# HAL_4.net
KiCad netlist of a schematic drawn in Altium Designer
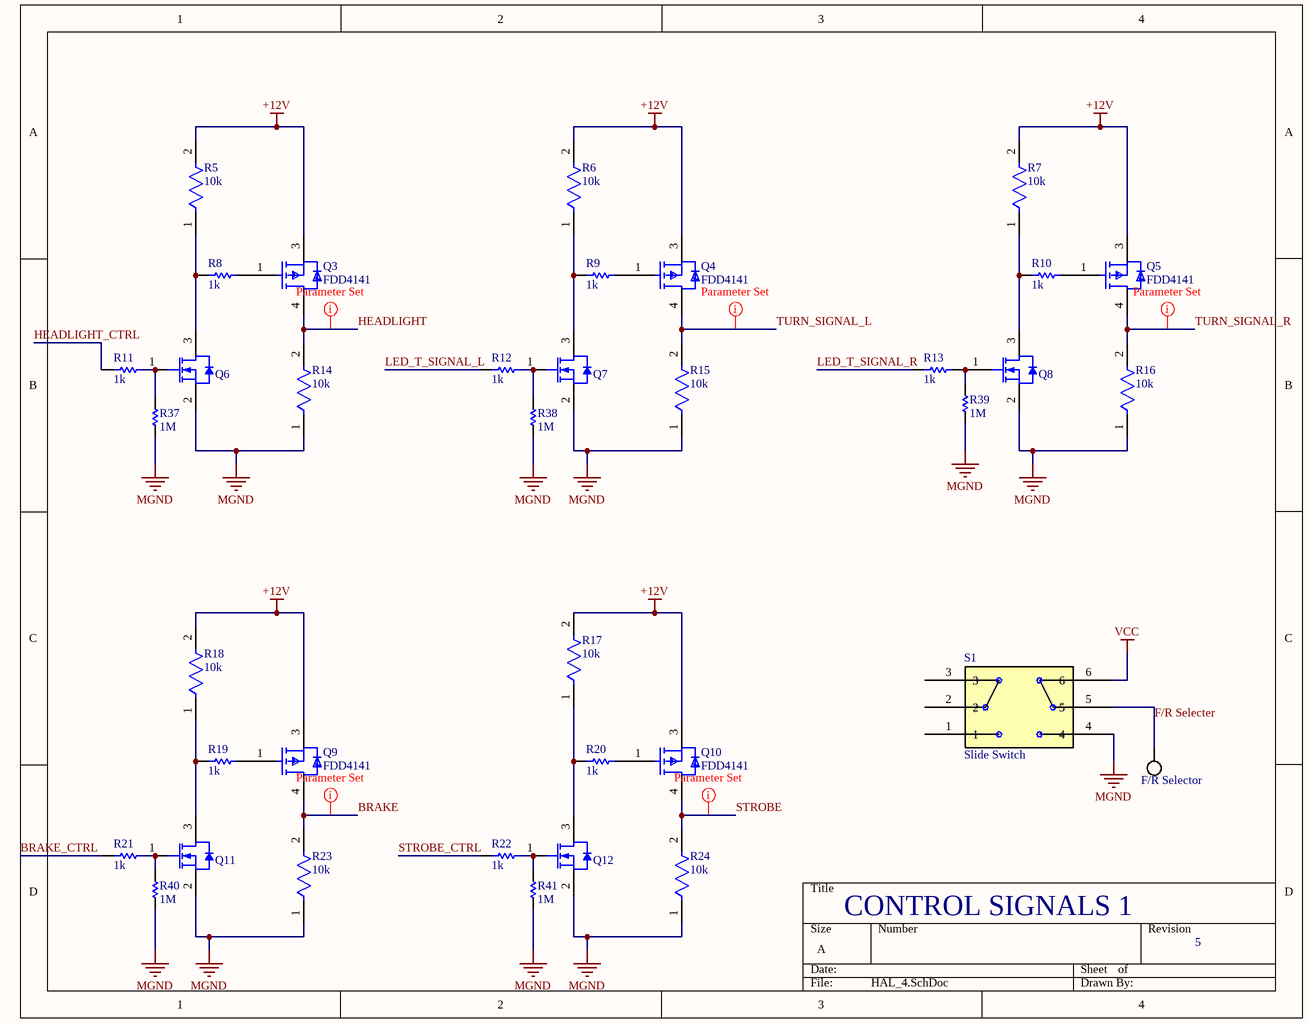
[diagram p0: HAL_4.SchDoc]

(export (version "E")
  (design (tool "Eeschema 10.0.6"))
  (components
    (comp (ref "F/R Selector")
      (value "F/R Selector")
      (footprint "EPAD")
      (description "Pad for probing signals")
      (libsource (lib "PrISUm-Discrete") (part "EPAD"))
    )
    (comp (ref "Q3")
      (value "FDD4141")
      (footprint "FP-369AS-MFG")
      (description "MOSFET P-CH 40V 10.8A DPAK")
      (fields
        (field (name "OCTOPART") "https://octopart.com/fdd4141-on+semiconductor-84325802")
        (field (name "MANUFACTURER") "ON Semiconductor")
      )
      (libsource (lib "Altium Content Vault") (part "ec195c925100855187fe8c06440c3e1"))
    )
    (comp (ref "Q4")
      (value "FDD4141")
      (footprint "FP-369AS-MFG")
      (description "MOSFET P-CH 40V 10.8A DPAK")
      (fields
        (field (name "OCTOPART") "https://octopart.com/fdd4141-on+semiconductor-84325802")
        (field (name "MANUFACTURER") "ON Semiconductor")
      )
      (libsource (lib "Altium Content Vault") (part "ec195c925100855187fe8c06440c3e1"))
    )
    (comp (ref "Q5")
      (value "FDD4141")
      (footprint "FP-369AS-MFG")
      (description "MOSFET P-CH 40V 10.8A DPAK")
      (fields
        (field (name "OCTOPART") "https://octopart.com/fdd4141-on+semiconductor-84325802")
        (field (name "MANUFACTURER") "ON Semiconductor")
      )
      (libsource (lib "Altium Content Vault") (part "ec195c925100855187fe8c06440c3e1"))
    )
    (comp (ref "Q6")
      (value "NTR4501NT1G")
      (footprint "ONSC-SOT-23-3-318-08_V")
      (description "Power MOSFET, 20 V, 3.2 A, Single N-Channel, 3-Pin SOT-23, Pb-Free, Tape and Reel")
      (fields (field (name "MANUFACTURER") "On Semiconductor"))
      (libsource (lib "Altium Content Vault") (part "ONSC-NMOS-G1S2D3-3"))
    )
    (comp (ref "Q7")
      (value "NTR4501NT1G")
      (footprint "ONSC-SOT-23-3-318-08_V")
      (description "Power MOSFET, 20 V, 3.2 A, Single N-Channel, 3-Pin SOT-23, Pb-Free, Tape and Reel")
      (fields (field (name "MANUFACTURER") "On Semiconductor"))
      (libsource (lib "Altium Content Vault") (part "ONSC-NMOS-G1S2D3-3"))
    )
    (comp (ref "Q8")
      (value "NTR4501NT1G")
      (footprint "ONSC-SOT-23-3-318-08_V")
      (description "Power MOSFET, 20 V, 3.2 A, Single N-Channel, 3-Pin SOT-23, Pb-Free, Tape and Reel")
      (fields (field (name "MANUFACTURER") "On Semiconductor"))
      (libsource (lib "Altium Content Vault") (part "ONSC-NMOS-G1S2D3-3"))
    )
    (comp (ref "Q9")
      (value "FDD4141")
      (footprint "FP-369AS-MFG")
      (description "MOSFET P-CH 40V 10.8A DPAK")
      (fields
        (field (name "OCTOPART") "https://octopart.com/fdd4141-on+semiconductor-84325802")
        (field (name "MANUFACTURER") "ON Semiconductor")
      )
      (libsource (lib "Altium Content Vault") (part "ec195c925100855187fe8c06440c3e1"))
    )
    (comp (ref "Q10")
      (value "FDD4141")
      (footprint "FP-369AS-MFG")
      (description "MOSFET P-CH 40V 10.8A DPAK")
      (fields
        (field (name "OCTOPART") "https://octopart.com/fdd4141-on+semiconductor-84325802")
        (field (name "MANUFACTURER") "ON Semiconductor")
      )
      (libsource (lib "Altium Content Vault") (part "ec195c925100855187fe8c06440c3e1"))
    )
    (comp (ref "Q11")
      (value "NTR4501NT1G")
      (footprint "ONSC-SOT-23-3-318-08_V")
      (description "Power MOSFET, 20 V, 3.2 A, Single N-Channel, 3-Pin SOT-23, Pb-Free, Tape and Reel")
      (fields (field (name "MANUFACTURER") "On Semiconductor"))
      (libsource (lib "Altium Content Vault") (part "ONSC-NMOS-G1S2D3-3"))
    )
    (comp (ref "Q12")
      (value "NTR4501NT1G")
      (footprint "ONSC-SOT-23-3-318-08_V")
      (description "Power MOSFET, 20 V, 3.2 A, Single N-Channel, 3-Pin SOT-23, Pb-Free, Tape and Reel")
      (fields (field (name "MANUFACTURER") "On Semiconductor"))
      (libsource (lib "Altium Content Vault") (part "ONSC-NMOS-G1S2D3-3"))
    )
    (comp (ref "R5")
      (value "10k")
      (footprint "FP-RMCF0805-MFG")
      (description "RES 10K OHM 1% 1/8W 0805")
      (fields (field (name "TOLERANCE") "1%"))
      (libsource (lib "Altium Content Vault") (part "1029c3af85768c4190bb7ad29bc67b5"))
    )
    (comp (ref "R6")
      (value "10k")
      (footprint "FP-RMCF0805-MFG")
      (description "RES 10K OHM 1% 1/8W 0805")
      (fields (field (name "TOLERANCE") "1%"))
      (libsource (lib "Altium Content Vault") (part "1029c3af85768c4190bb7ad29bc67b5"))
    )
    (comp (ref "R7")
      (value "10k")
      (footprint "FP-RMCF0805-MFG")
      (description "RES 10K OHM 1% 1/8W 0805")
      (fields (field (name "TOLERANCE") "1%"))
      (libsource (lib "Altium Content Vault") (part "1029c3af85768c4190bb7ad29bc67b5"))
    )
    (comp (ref "R8")
      (value "1k")
      (footprint "RESC3216X70X40LL20T20")
      (description "RK73B2BTTD102J")
      (fields (field (name "MANUFACTURER") "KOA Speer"))
      (libsource (lib "Altium Content Vault") (part "RES"))
    )
    (comp (ref "R9")
      (value "1k")
      (footprint "RESC3216X70X40LL20T20")
      (description "RK73B2BTTD102J")
      (fields (field (name "MANUFACTURER") "KOA Speer"))
      (libsource (lib "Altium Content Vault") (part "RES"))
    )
    (comp (ref "R10")
      (value "1k")
      (footprint "RESC3216X70X40LL20T20")
      (description "RK73B2BTTD102J")
      (fields (field (name "MANUFACTURER") "KOA Speer"))
      (libsource (lib "Altium Content Vault") (part "RES"))
    )
    (comp (ref "R11")
      (value "1k")
      (footprint "RESC3216X70X40LL20T20")
      (description "RK73B2BTTD102J")
      (fields (field (name "MANUFACTURER") "KOA Speer"))
      (libsource (lib "Altium Content Vault") (part "RES"))
    )
    (comp (ref "R12")
      (value "1k")
      (footprint "RESC3216X70X40LL20T20")
      (description "RK73B2BTTD102J")
      (fields (field (name "MANUFACTURER") "KOA Speer"))
      (libsource (lib "Altium Content Vault") (part "RES"))
    )
    (comp (ref "R13")
      (value "1k")
      (footprint "RESC3216X70X40LL20T20")
      (description "RK73B2BTTD102J")
      (fields (field (name "MANUFACTURER") "KOA Speer"))
      (libsource (lib "Altium Content Vault") (part "RES"))
    )
    (comp (ref "R14")
      (value "10k")
      (footprint "FP-RMCF0805-MFG")
      (description "RES 10K OHM 1% 1/8W 0805")
      (fields (field (name "TOLERANCE") "1%"))
      (libsource (lib "Altium Content Vault") (part "1029c3af85768c4190bb7ad29bc67b5"))
    )
    (comp (ref "R15")
      (value "10k")
      (footprint "FP-RMCF0805-MFG")
      (description "RES 10K OHM 1% 1/8W 0805")
      (fields (field (name "TOLERANCE") "1%"))
      (libsource (lib "Altium Content Vault") (part "1029c3af85768c4190bb7ad29bc67b5"))
    )
    (comp (ref "R16")
      (value "10k")
      (footprint "FP-RMCF0805-MFG")
      (description "RES 10K OHM 1% 1/8W 0805")
      (fields (field (name "TOLERANCE") "1%"))
      (libsource (lib "Altium Content Vault") (part "1029c3af85768c4190bb7ad29bc67b5"))
    )
    (comp (ref "R17")
      (value "10k")
      (footprint "FP-RMCF0805-MFG")
      (description "RES 10K OHM 1% 1/8W 0805")
      (fields (field (name "TOLERANCE") "1%"))
      (libsource (lib "Altium Content Vault") (part "1029c3af85768c4190bb7ad29bc67b5"))
    )
    (comp (ref "R18")
      (value "10k")
      (footprint "FP-RMCF0805-MFG")
      (description "RES 10K OHM 1% 1/8W 0805")
      (fields (field (name "TOLERANCE") "1%"))
      (libsource (lib "Altium Content Vault") (part "1029c3af85768c4190bb7ad29bc67b5"))
    )
    (comp (ref "R19")
      (value "1k")
      (footprint "RESC3216X70X40LL20T20")
      (description "RK73B2BTTD102J")
      (fields (field (name "MANUFACTURER") "KOA Speer"))
      (libsource (lib "Altium Content Vault") (part "RES"))
    )
    (comp (ref "R20")
      (value "1k")
      (footprint "RESC3216X70X40LL20T20")
      (description "RK73B2BTTD102J")
      (fields (field (name "MANUFACTURER") "KOA Speer"))
      (libsource (lib "Altium Content Vault") (part "RES"))
    )
    (comp (ref "R21")
      (value "1k")
      (footprint "RESC3216X70X40LL20T20")
      (description "RK73B2BTTD102J")
      (fields (field (name "MANUFACTURER") "KOA Speer"))
      (libsource (lib "Altium Content Vault") (part "RES"))
    )
    (comp (ref "R22")
      (value "1k")
      (footprint "RESC3216X70X40LL20T20")
      (description "RK73B2BTTD102J")
      (fields (field (name "MANUFACTURER") "KOA Speer"))
      (libsource (lib "Altium Content Vault") (part "RES"))
    )
    (comp (ref "R23")
      (value "10k")
      (footprint "FP-RMCF0805-MFG")
      (description "RES 10K OHM 1% 1/8W 0805")
      (fields (field (name "TOLERANCE") "1%"))
      (libsource (lib "Altium Content Vault") (part "1029c3af85768c4190bb7ad29bc67b5"))
    )
    (comp (ref "R24")
      (value "10k")
      (footprint "FP-RMCF0805-MFG")
      (description "RES 10K OHM 1% 1/8W 0805")
      (fields (field (name "TOLERANCE") "1%"))
      (libsource (lib "Altium Content Vault") (part "1029c3af85768c4190bb7ad29bc67b5"))
    )
    (comp (ref "R37")
      (value "1M")
      (footprint "0603_B")
      (description "0603 1MOhm resistor")
      (fields (field (name "Comment") "CRCW06031M00FKEA"))
      (libsource (lib "Resistors") (part "CRCW06031M00FKEA"))
    )
    (comp (ref "R38")
      (value "1M")
      (footprint "0603_B")
      (description "0603 1MOhm resistor")
      (fields (field (name "Comment") "CRCW06031M00FKEA"))
      (libsource (lib "Resistors") (part "CRCW06031M00FKEA"))
    )
    (comp (ref "R39")
      (value "1M")
      (footprint "0603_B")
      (description "0603 1MOhm resistor")
      (fields (field (name "Comment") "CRCW06031M00FKEA"))
      (libsource (lib "Resistors") (part "CRCW06031M00FKEA"))
    )
    (comp (ref "R40")
      (value "1M")
      (footprint "0603_B")
      (description "0603 1MOhm resistor")
      (fields (field (name "Comment") "CRCW06031M00FKEA"))
      (libsource (lib "Resistors") (part "CRCW06031M00FKEA"))
    )
    (comp (ref "R41")
      (value "1M")
      (footprint "0603_B")
      (description "0603 1MOhm resistor")
      (fields (field (name "Comment") "CRCW06031M00FKEA"))
      (libsource (lib "Resistors") (part "CRCW06031M00FKEA"))
    )
    (comp (ref "S1")
      (value "Slide Switch")
      (footprint "DPDT Switch")
      (libsource (lib "PrISUm-Discrete") (part "Slide Switch"))
    )
  )
  (nets
    (net (code "1") (name "+12V") (class "Default")
      (node (ref "Q10") (pin "3") (pinfunction "S_3") (pintype "passive"))
      (node (ref "Q3") (pin "3") (pinfunction "S_3") (pintype "passive"))
      (node (ref "Q4") (pin "3") (pinfunction "S_3") (pintype "passive"))
      (node (ref "Q5") (pin "3") (pinfunction "S_3") (pintype "passive"))
      (node (ref "Q9") (pin "3") (pinfunction "S_3") (pintype "passive"))
      (node (ref "R17") (pin "2") (pinfunction "2_2") (pintype "passive"))
      (node (ref "R18") (pin "2") (pinfunction "2_2") (pintype "passive"))
      (node (ref "R5") (pin "2") (pinfunction "2_2") (pintype "passive"))
      (node (ref "R6") (pin "2") (pinfunction "2_2") (pintype "passive"))
      (node (ref "R7") (pin "2") (pinfunction "2_2") (pintype "passive"))
    )
    (net (code "2") (name "/BRAKE") (class "Default")
      (node (ref "Q9") (pin "4") (pinfunction "D_4") (pintype "passive"))
      (node (ref "R23") (pin "2") (pinfunction "2_2") (pintype "passive"))
    )
    (net (code "3") (name "/BRAKE_CTRL") (class "Default")
      (node (ref "R21") (pin "1") (pinfunction "1_1") (pintype "passive"))
    )
    (net (code "4") (name "/F{slash}R Selecter") (class "Default")
      (node (ref "F/R Selector") (pin "1") (pinfunction "1_1") (pintype "passive"))
      (node (ref "S1") (pin "5") (pinfunction "5_5") (pintype "passive"))
    )
    (net (code "5") (name "/HEADLIGHT") (class "Default")
      (node (ref "Q3") (pin "4") (pinfunction "D_4") (pintype "passive"))
      (node (ref "R14") (pin "2") (pinfunction "2_2") (pintype "passive"))
    )
    (net (code "6") (name "/HEADLIGHT_CTRL") (class "Default")
      (node (ref "R11") (pin "1") (pinfunction "1_1") (pintype "passive"))
    )
    (net (code "7") (name "/LED_T_SIGNAL_L") (class "Default")
      (node (ref "R12") (pin "1") (pinfunction "1_1") (pintype "passive"))
    )
    (net (code "8") (name "/LED_T_SIGNAL_R") (class "Default")
      (node (ref "R13") (pin "1") (pinfunction "1_1") (pintype "passive"))
    )
    (net (code "9") (name "/STROBE") (class "Default")
      (node (ref "Q10") (pin "4") (pinfunction "D_4") (pintype "passive"))
      (node (ref "R24") (pin "2") (pinfunction "2_2") (pintype "passive"))
    )
    (net (code "10") (name "/STROBE_CTRL") (class "Default")
      (node (ref "R22") (pin "1") (pinfunction "1_1") (pintype "passive"))
    )
    (net (code "11") (name "/TURN_SIGNAL_L") (class "Default")
      (node (ref "Q4") (pin "4") (pinfunction "D_4") (pintype "passive"))
      (node (ref "R15") (pin "2") (pinfunction "2_2") (pintype "passive"))
    )
    (net (code "12") (name "/TURN_SIGNAL_R") (class "Default")
      (node (ref "Q5") (pin "4") (pinfunction "D_4") (pintype "passive"))
      (node (ref "R16") (pin "2") (pinfunction "2_2") (pintype "passive"))
    )
    (net (code "13") (name "MGND") (class "Default")
      (node (ref "Q11") (pin "2") (pinfunction "S_2") (pintype "passive"))
      (node (ref "Q12") (pin "2") (pinfunction "S_2") (pintype "passive"))
      (node (ref "Q6") (pin "2") (pinfunction "S_2") (pintype "passive"))
      (node (ref "Q7") (pin "2") (pinfunction "S_2") (pintype "passive"))
      (node (ref "Q8") (pin "2") (pinfunction "S_2") (pintype "passive"))
      (node (ref "R14") (pin "1") (pinfunction "1_1") (pintype "passive"))
      (node (ref "R15") (pin "1") (pinfunction "1_1") (pintype "passive"))
      (node (ref "R16") (pin "1") (pinfunction "1_1") (pintype "passive"))
      (node (ref "R23") (pin "1") (pinfunction "1_1") (pintype "passive"))
      (node (ref "R24") (pin "1") (pinfunction "1_1") (pintype "passive"))
      (node (ref "R37") (pin "1") (pinfunction "1_1") (pintype "passive"))
      (node (ref "R38") (pin "1") (pinfunction "1_1") (pintype "passive"))
      (node (ref "R39") (pin "1") (pinfunction "1_1") (pintype "passive"))
      (node (ref "R40") (pin "1") (pinfunction "1_1") (pintype "passive"))
      (node (ref "R41") (pin "1") (pinfunction "1_1") (pintype "passive"))
      (node (ref "S1") (pin "4") (pinfunction "4_4") (pintype "passive"))
    )
    (net (code "14") (name "Net-(Q3-G)") (class "Default")
      (node (ref "Q3") (pin "1") (pinfunction "G_1") (pintype "passive"))
      (node (ref "R8") (pin "2") (pinfunction "2_2") (pintype "passive"))
    )
    (net (code "15") (name "Net-(Q4-G)") (class "Default")
      (node (ref "Q4") (pin "1") (pinfunction "G_1") (pintype "passive"))
      (node (ref "R9") (pin "2") (pinfunction "2_2") (pintype "passive"))
    )
    (net (code "16") (name "Net-(Q5-G)") (class "Default")
      (node (ref "Q5") (pin "1") (pinfunction "G_1") (pintype "passive"))
      (node (ref "R10") (pin "2") (pinfunction "2_2") (pintype "passive"))
    )
    (net (code "17") (name "Net-(Q6-D)") (class "Default")
      (node (ref "Q6") (pin "3") (pinfunction "D_3") (pintype "passive"))
      (node (ref "R5") (pin "1") (pinfunction "1_1") (pintype "passive"))
      (node (ref "R8") (pin "1") (pinfunction "1_1") (pintype "passive"))
    )
    (net (code "18") (name "Net-(Q6-G)") (class "Default")
      (node (ref "Q6") (pin "1") (pinfunction "G_1") (pintype "passive"))
      (node (ref "R11") (pin "2") (pinfunction "2_2") (pintype "passive"))
      (node (ref "R37") (pin "2") (pinfunction "2_2") (pintype "passive"))
    )
    (net (code "19") (name "Net-(Q7-D)") (class "Default")
      (node (ref "Q7") (pin "3") (pinfunction "D_3") (pintype "passive"))
      (node (ref "R6") (pin "1") (pinfunction "1_1") (pintype "passive"))
      (node (ref "R9") (pin "1") (pinfunction "1_1") (pintype "passive"))
    )
    (net (code "20") (name "Net-(Q7-G)") (class "Default")
      (node (ref "Q7") (pin "1") (pinfunction "G_1") (pintype "passive"))
      (node (ref "R12") (pin "2") (pinfunction "2_2") (pintype "passive"))
      (node (ref "R38") (pin "2") (pinfunction "2_2") (pintype "passive"))
    )
    (net (code "21") (name "Net-(Q8-D)") (class "Default")
      (node (ref "Q8") (pin "3") (pinfunction "D_3") (pintype "passive"))
      (node (ref "R10") (pin "1") (pinfunction "1_1") (pintype "passive"))
      (node (ref "R7") (pin "1") (pinfunction "1_1") (pintype "passive"))
    )
    (net (code "22") (name "Net-(Q8-G)") (class "Default")
      (node (ref "Q8") (pin "1") (pinfunction "G_1") (pintype "passive"))
      (node (ref "R13") (pin "2") (pinfunction "2_2") (pintype "passive"))
      (node (ref "R39") (pin "2") (pinfunction "2_2") (pintype "passive"))
    )
    (net (code "23") (name "Net-(Q9-G)") (class "Default")
      (node (ref "Q9") (pin "1") (pinfunction "G_1") (pintype "passive"))
      (node (ref "R19") (pin "2") (pinfunction "2_2") (pintype "passive"))
    )
    (net (code "24") (name "Net-(Q10-G)") (class "Default")
      (node (ref "Q10") (pin "1") (pinfunction "G_1") (pintype "passive"))
      (node (ref "R20") (pin "2") (pinfunction "2_2") (pintype "passive"))
    )
    (net (code "25") (name "Net-(Q11-D)") (class "Default")
      (node (ref "Q11") (pin "3") (pinfunction "D_3") (pintype "passive"))
      (node (ref "R18") (pin "1") (pinfunction "1_1") (pintype "passive"))
      (node (ref "R19") (pin "1") (pinfunction "1_1") (pintype "passive"))
    )
    (net (code "26") (name "Net-(Q11-G)") (class "Default")
      (node (ref "Q11") (pin "1") (pinfunction "G_1") (pintype "passive"))
      (node (ref "R21") (pin "2") (pinfunction "2_2") (pintype "passive"))
      (node (ref "R40") (pin "2") (pinfunction "2_2") (pintype "passive"))
    )
    (net (code "27") (name "Net-(Q12-D)") (class "Default")
      (node (ref "Q12") (pin "3") (pinfunction "D_3") (pintype "passive"))
      (node (ref "R17") (pin "1") (pinfunction "1_1") (pintype "passive"))
      (node (ref "R20") (pin "1") (pinfunction "1_1") (pintype "passive"))
    )
    (net (code "28") (name "Net-(Q12-G)") (class "Default")
      (node (ref "Q12") (pin "1") (pinfunction "G_1") (pintype "passive"))
      (node (ref "R22") (pin "2") (pinfunction "2_2") (pintype "passive"))
      (node (ref "R41") (pin "2") (pinfunction "2_2") (pintype "passive"))
    )
    (net (code "29") (name "VCC") (class "Default")
      (node (ref "S1") (pin "6") (pinfunction "6_6") (pintype "passive"))
    )
    (net (code "30") (name "unconnected-(S1-Pad1)") (class "Default")
      (node (ref "S1") (pin "1") (pinfunction "1_1") (pintype "passive"))
    )
    (net (code "31") (name "unconnected-(S1-Pad2)") (class "Default")
      (node (ref "S1") (pin "2") (pinfunction "2_2") (pintype "passive"))
    )
    (net (code "32") (name "unconnected-(S1-Pad3)") (class "Default")
      (node (ref "S1") (pin "3") (pinfunction "3_3") (pintype "passive"))
    )
  )
)
